# l297.net
KiCad netlist of a schematic drawn in EAGLE
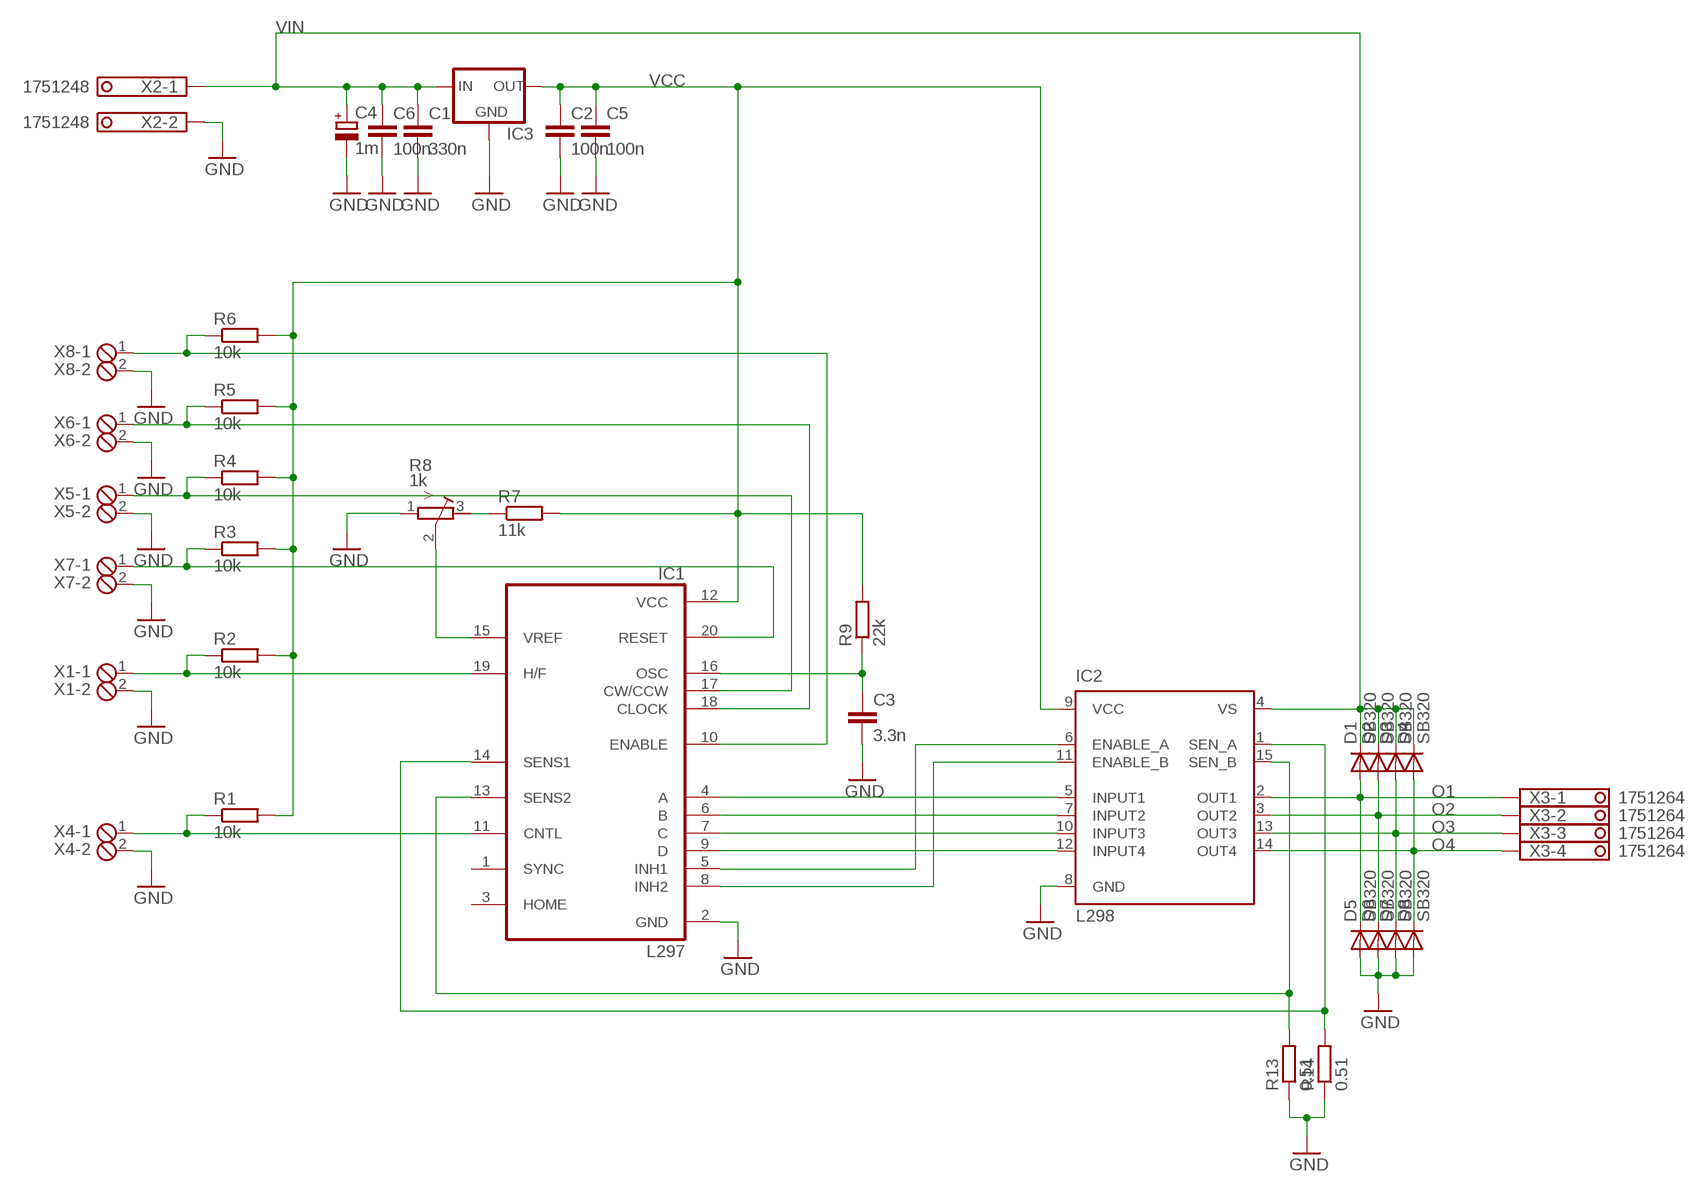
[diagram p0: schematic, sheet 1]

(export (version "E")
  (design (tool "Eeschema 10.0.6"))
  (components
    (comp (ref "C1")
      (value "330n")
      (footprint "eagle-import:C050-035X075")
      (libsource (lib "eagle-import") (part "C-EU050-035X075"))
    )
    (comp (ref "C2")
      (value "100n")
      (footprint "eagle-import:C050-035X075")
      (libsource (lib "eagle-import") (part "C-EU050-035X075"))
    )
    (comp (ref "C3")
      (value "3.3n")
      (footprint "eagle-import:C050-035X075")
      (libsource (lib "eagle-import") (part "C-EU050-035X075"))
    )
    (comp (ref "C4")
      (value "1m")
      (footprint "eagle-import:E5-13")
      (libsource (lib "eagle-import") (part "CPOL-EUE5-13"))
    )
    (comp (ref "C5")
      (value "100n")
      (footprint "eagle-import:C050-035X075")
      (libsource (lib "eagle-import") (part "C-EU050-035X075"))
    )
    (comp (ref "C6")
      (value "100n")
      (footprint "eagle-import:C050-035X075")
      (libsource (lib "eagle-import") (part "C-EU050-035X075"))
    )
    (comp (ref "D1")
      (value "SB320")
      (footprint "eagle-import:DO201-15")
      (libsource (lib "eagle-import") (part "SB320"))
    )
    (comp (ref "D2")
      (value "SB320")
      (footprint "eagle-import:DO201-15")
      (libsource (lib "eagle-import") (part "SB320"))
    )
    (comp (ref "D3")
      (value "SB320")
      (footprint "eagle-import:DO201-15")
      (libsource (lib "eagle-import") (part "SB320"))
    )
    (comp (ref "D4")
      (value "SB320")
      (footprint "eagle-import:DO201-15")
      (libsource (lib "eagle-import") (part "SB320"))
    )
    (comp (ref "D5")
      (value "SB320")
      (footprint "eagle-import:DO201-15")
      (libsource (lib "eagle-import") (part "SB320"))
    )
    (comp (ref "D6")
      (value "SB320")
      (footprint "eagle-import:DO201-15")
      (libsource (lib "eagle-import") (part "SB320"))
    )
    (comp (ref "D7")
      (value "SB320")
      (footprint "eagle-import:DO201-15")
      (libsource (lib "eagle-import") (part "SB320"))
    )
    (comp (ref "D8")
      (value "SB320")
      (footprint "eagle-import:DO201-15")
      (libsource (lib "eagle-import") (part "SB320"))
    )
    (comp (ref "IC1")
      (value "L297")
      (footprint "eagle-import:DIL20")
      (fields (field (name "MPN") "L297/1"))
      (libsource (lib "eagle-import") (part "L297"))
    )
    (comp (ref "IC2")
      (value "L298")
      (footprint "eagle-import:MULTIWATT-15")
      (fields (field (name "MPN") "L298N"))
      (libsource (lib "eagle-import") (part "L298"))
    )
    (comp (ref "IC3")
      (value "78XXS")
      (footprint "eagle-import:78XXS")
      (libsource (lib "eagle-import") (part "78XXS"))
    )
    (comp (ref "R1")
      (value "10k")
      (footprint "eagle-import:0207_10")
      (libsource (lib "eagle-import") (part "R-EU_0207/10"))
    )
    (comp (ref "R2")
      (value "10k")
      (footprint "eagle-import:0207_10")
      (libsource (lib "eagle-import") (part "R-EU_0207/10"))
    )
    (comp (ref "R3")
      (value "10k")
      (footprint "eagle-import:0207_10")
      (libsource (lib "eagle-import") (part "R-EU_0207/10"))
    )
    (comp (ref "R4")
      (value "10k")
      (footprint "eagle-import:0207_10")
      (libsource (lib "eagle-import") (part "R-EU_0207/10"))
    )
    (comp (ref "R5")
      (value "10k")
      (footprint "eagle-import:0207_10")
      (libsource (lib "eagle-import") (part "R-EU_0207/10"))
    )
    (comp (ref "R6")
      (value "10k")
      (footprint "eagle-import:0207_10")
      (libsource (lib "eagle-import") (part "R-EU_0207/10"))
    )
    (comp (ref "R7")
      (value "11k")
      (footprint "eagle-import:0207_10")
      (libsource (lib "eagle-import") (part "R-EU_0207/10"))
    )
    (comp (ref "R8")
      (value "1k")
      (footprint "eagle-import:RTRIM64W")
      (libsource (lib "eagle-import") (part "R-TRIMM64W"))
    )
    (comp (ref "R9")
      (value "22k")
      (footprint "eagle-import:0207_10")
      (libsource (lib "eagle-import") (part "R-EU_0207/10"))
    )
    (comp (ref "R13")
      (value "0.51")
      (footprint "eagle-import:0411_15")
      (libsource (lib "eagle-import") (part "R-EU_0411/15"))
    )
    (comp (ref "R14")
      (value "0.51")
      (footprint "eagle-import:0411_15")
      (libsource (lib "eagle-import") (part "R-EU_0411/15"))
    )
    (comp (ref "X1")
      (value "MPT2")
      (footprint "eagle-import:2POL254")
      (libsource (lib "eagle-import") (part "MPT2"))
    )
    (comp (ref "X2")
      (value "1751248")
      (footprint "eagle-import:1751248")
      (libsource (lib "eagle-import") (part "1751248"))
    )
    (comp (ref "X3")
      (value "1751264")
      (footprint "eagle-import:1751264")
      (libsource (lib "eagle-import") (part "1751264"))
    )
    (comp (ref "X4")
      (value "MPT2")
      (footprint "eagle-import:2POL254")
      (libsource (lib "eagle-import") (part "MPT2"))
    )
    (comp (ref "X5")
      (value "MPT2")
      (footprint "eagle-import:2POL254")
      (libsource (lib "eagle-import") (part "MPT2"))
    )
    (comp (ref "X6")
      (value "MPT2")
      (footprint "eagle-import:2POL254")
      (libsource (lib "eagle-import") (part "MPT2"))
    )
    (comp (ref "X7")
      (value "MPT2")
      (footprint "eagle-import:2POL254")
      (libsource (lib "eagle-import") (part "MPT2"))
    )
    (comp (ref "X8")
      (value "MPT2")
      (footprint "eagle-import:2POL254")
      (libsource (lib "eagle-import") (part "MPT2"))
    )
  )
  (nets
    (net (code "1") (name "/O1") (class "Default")
      (node (ref "D1") (pin "A") (pinfunction "A_A") (pintype "passive"))
      (node (ref "D5") (pin "C") (pinfunction "C_C") (pintype "passive"))
      (node (ref "IC2") (pin "2") (pinfunction "OUT1_2") (pintype "output"))
      (node (ref "X3") (pin "1") (pinfunction "K_1") (pintype "passive"))
    )
    (net (code "2") (name "/O2") (class "Default")
      (node (ref "D2") (pin "A") (pinfunction "A_A") (pintype "passive"))
      (node (ref "D6") (pin "C") (pinfunction "C_C") (pintype "passive"))
      (node (ref "IC2") (pin "3") (pinfunction "OUT2_3") (pintype "output"))
      (node (ref "X3") (pin "2") (pinfunction "K_2") (pintype "passive"))
    )
    (net (code "3") (name "/O3") (class "Default")
      (node (ref "D3") (pin "A") (pinfunction "A_A") (pintype "passive"))
      (node (ref "D7") (pin "C") (pinfunction "C_C") (pintype "passive"))
      (node (ref "IC2") (pin "13") (pinfunction "OUT3_13") (pintype "output"))
      (node (ref "X3") (pin "3") (pinfunction "K_3") (pintype "passive"))
    )
    (net (code "4") (name "/O4") (class "Default")
      (node (ref "D4") (pin "A") (pinfunction "A_A") (pintype "passive"))
      (node (ref "D8") (pin "C") (pinfunction "C_C") (pintype "passive"))
      (node (ref "IC2") (pin "14") (pinfunction "OUT4_14") (pintype "output"))
      (node (ref "X3") (pin "4") (pinfunction "K_4") (pintype "passive"))
    )
    (net (code "5") (name "/VCC") (class "Default")
      (node (ref "C2") (pin "1") (pinfunction "1_1") (pintype "passive"))
      (node (ref "C5") (pin "1") (pinfunction "1_1") (pintype "passive"))
      (node (ref "IC1") (pin "12") (pinfunction "VCC_12") (pintype "power_in"))
      (node (ref "IC2") (pin "9") (pinfunction "VCC_9") (pintype "power_in"))
      (node (ref "IC3") (pin "OUT") (pinfunction "OUT_OUT") (pintype "passive"))
      (node (ref "R1") (pin "2") (pinfunction "2_2") (pintype "passive"))
      (node (ref "R2") (pin "2") (pinfunction "2_2") (pintype "passive"))
      (node (ref "R3") (pin "2") (pinfunction "2_2") (pintype "passive"))
      (node (ref "R4") (pin "2") (pinfunction "2_2") (pintype "passive"))
      (node (ref "R5") (pin "2") (pinfunction "2_2") (pintype "passive"))
      (node (ref "R6") (pin "2") (pinfunction "2_2") (pintype "passive"))
      (node (ref "R7") (pin "2") (pinfunction "2_2") (pintype "passive"))
      (node (ref "R9") (pin "2") (pinfunction "2_2") (pintype "passive"))
    )
    (net (code "6") (name "/VIN") (class "Default")
      (node (ref "C1") (pin "1") (pinfunction "1_1") (pintype "passive"))
      (node (ref "C4") (pin "+") (pinfunction "+_+") (pintype "passive"))
      (node (ref "C6") (pin "1") (pinfunction "1_1") (pintype "passive"))
      (node (ref "D1") (pin "C") (pinfunction "C_C") (pintype "passive"))
      (node (ref "D2") (pin "C") (pinfunction "C_C") (pintype "passive"))
      (node (ref "D3") (pin "C") (pinfunction "C_C") (pintype "passive"))
      (node (ref "D4") (pin "C") (pinfunction "C_C") (pintype "passive"))
      (node (ref "IC2") (pin "4") (pinfunction "VS_4") (pintype "power_in"))
      (node (ref "IC3") (pin "IN") (pinfunction "IN_IN") (pintype "input"))
      (node (ref "X2") (pin "1") (pinfunction "K_1") (pintype "passive"))
    )
    (net (code "7") (name "GND") (class "Default")
      (node (ref "C1") (pin "2") (pinfunction "2_2") (pintype "passive"))
      (node (ref "C2") (pin "2") (pinfunction "2_2") (pintype "passive"))
      (node (ref "C3") (pin "2") (pinfunction "2_2") (pintype "passive"))
      (node (ref "C4") (pin "-") (pinfunction "-_-") (pintype "passive"))
      (node (ref "C5") (pin "2") (pinfunction "2_2") (pintype "passive"))
      (node (ref "C6") (pin "2") (pinfunction "2_2") (pintype "passive"))
      (node (ref "D5") (pin "A") (pinfunction "A_A") (pintype "passive"))
      (node (ref "D6") (pin "A") (pinfunction "A_A") (pintype "passive"))
      (node (ref "D7") (pin "A") (pinfunction "A_A") (pintype "passive"))
      (node (ref "D8") (pin "A") (pinfunction "A_A") (pintype "passive"))
      (node (ref "IC1") (pin "2") (pinfunction "GND_2") (pintype "power_in"))
      (node (ref "IC2") (pin "8") (pinfunction "GND_8") (pintype "power_in"))
      (node (ref "IC3") (pin "GND") (pinfunction "GND_GND") (pintype "input"))
      (node (ref "R13") (pin "1") (pinfunction "1_1") (pintype "passive"))
      (node (ref "R14") (pin "1") (pinfunction "1_1") (pintype "passive"))
      (node (ref "R8") (pin "1") (pinfunction "E_1") (pintype "passive"))
      (node (ref "X1") (pin "2") (pinfunction "1_2") (pintype "passive"))
      (node (ref "X2") (pin "2") (pinfunction "K_2") (pintype "passive"))
      (node (ref "X4") (pin "2") (pinfunction "1_2") (pintype "passive"))
      (node (ref "X5") (pin "2") (pinfunction "1_2") (pintype "passive"))
      (node (ref "X6") (pin "2") (pinfunction "1_2") (pintype "passive"))
      (node (ref "X7") (pin "2") (pinfunction "1_2") (pintype "passive"))
      (node (ref "X8") (pin "2") (pinfunction "1_2") (pintype "passive"))
    )
    (net (code "8") (name "Net-(IC1-A)") (class "Default")
      (node (ref "IC1") (pin "4") (pinfunction "A_4") (pintype "output"))
      (node (ref "IC2") (pin "5") (pinfunction "INPUT1_5") (pintype "input"))
    )
    (net (code "9") (name "Net-(IC1-B)") (class "Default")
      (node (ref "IC1") (pin "6") (pinfunction "B_6") (pintype "output"))
      (node (ref "IC2") (pin "7") (pinfunction "INPUT2_7") (pintype "input"))
    )
    (net (code "10") (name "Net-(IC1-C)") (class "Default")
      (node (ref "IC1") (pin "7") (pinfunction "C_7") (pintype "output"))
      (node (ref "IC2") (pin "10") (pinfunction "INPUT3_10") (pintype "input"))
    )
    (net (code "11") (name "Net-(IC1-CLOCK)") (class "Default")
      (node (ref "IC1") (pin "18") (pinfunction "CLOCK_18") (pintype "input"))
      (node (ref "R5") (pin "1") (pinfunction "1_1") (pintype "passive"))
      (node (ref "X6") (pin "1") (pinfunction "1_1") (pintype "passive"))
    )
    (net (code "12") (name "Net-(IC1-CNTL)") (class "Default")
      (node (ref "IC1") (pin "11") (pinfunction "CNTL_11") (pintype "input"))
      (node (ref "R1") (pin "1") (pinfunction "1_1") (pintype "passive"))
      (node (ref "X4") (pin "1") (pinfunction "1_1") (pintype "passive"))
    )
    (net (code "13") (name "Net-(IC1-CW{slash}CCW)") (class "Default")
      (node (ref "IC1") (pin "17") (pinfunction "CW/CCW_17") (pintype "input"))
      (node (ref "R4") (pin "1") (pinfunction "1_1") (pintype "passive"))
      (node (ref "X5") (pin "1") (pinfunction "1_1") (pintype "passive"))
    )
    (net (code "14") (name "Net-(IC1-D)") (class "Default")
      (node (ref "IC1") (pin "9") (pinfunction "D_9") (pintype "output"))
      (node (ref "IC2") (pin "12") (pinfunction "INPUT4_12") (pintype "input"))
    )
    (net (code "15") (name "Net-(IC1-ENABLE)") (class "Default")
      (node (ref "IC1") (pin "10") (pinfunction "ENABLE_10") (pintype "input"))
      (node (ref "R6") (pin "1") (pinfunction "1_1") (pintype "passive"))
      (node (ref "X8") (pin "1") (pinfunction "1_1") (pintype "passive"))
    )
    (net (code "16") (name "Net-(IC1-H{slash}F)") (class "Default")
      (node (ref "IC1") (pin "19") (pinfunction "H/F_19") (pintype "input"))
      (node (ref "R2") (pin "1") (pinfunction "1_1") (pintype "passive"))
      (node (ref "X1") (pin "1") (pinfunction "1_1") (pintype "passive"))
    )
    (net (code "17") (name "Net-(IC1-INH1)") (class "Default")
      (node (ref "IC1") (pin "5") (pinfunction "INH1_5") (pintype "output"))
      (node (ref "IC2") (pin "6") (pinfunction "ENABLE_A_6") (pintype "input"))
    )
    (net (code "18") (name "Net-(IC1-INH2)") (class "Default")
      (node (ref "IC1") (pin "8") (pinfunction "INH2_8") (pintype "output"))
      (node (ref "IC2") (pin "11") (pinfunction "ENABLE_B_11") (pintype "input"))
    )
    (net (code "19") (name "Net-(IC1-OSC)") (class "Default")
      (node (ref "C3") (pin "1") (pinfunction "1_1") (pintype "passive"))
      (node (ref "IC1") (pin "16") (pinfunction "OSC_16") (pintype "bidirectional"))
      (node (ref "R9") (pin "1") (pinfunction "1_1") (pintype "passive"))
    )
    (net (code "20") (name "Net-(IC1-RESET)") (class "Default")
      (node (ref "IC1") (pin "20") (pinfunction "RESET_20") (pintype "input"))
      (node (ref "R3") (pin "1") (pinfunction "1_1") (pintype "passive"))
      (node (ref "X7") (pin "1") (pinfunction "1_1") (pintype "passive"))
    )
    (net (code "21") (name "Net-(IC1-SENS1)") (class "Default")
      (node (ref "IC1") (pin "14") (pinfunction "SENS1_14") (pintype "output"))
      (node (ref "IC2") (pin "1") (pinfunction "SEN_A_1") (pintype "input"))
      (node (ref "R14") (pin "2") (pinfunction "2_2") (pintype "passive"))
    )
    (net (code "22") (name "Net-(IC1-SENS2)") (class "Default")
      (node (ref "IC1") (pin "13") (pinfunction "SENS2_13") (pintype "output"))
      (node (ref "IC2") (pin "15") (pinfunction "SEN_B_15") (pintype "input"))
      (node (ref "R13") (pin "2") (pinfunction "2_2") (pintype "passive"))
    )
    (net (code "23") (name "Net-(IC1-VREF)") (class "Default")
      (node (ref "IC1") (pin "15") (pinfunction "VREF_15") (pintype "input"))
      (node (ref "R8") (pin "2") (pinfunction "S_2") (pintype "passive"))
    )
    (net (code "24") (name "Net-(R8-A)") (class "Default")
      (node (ref "R7") (pin "1") (pinfunction "1_1") (pintype "passive"))
      (node (ref "R8") (pin "3") (pinfunction "A_3") (pintype "passive"))
    )
    (net (code "25") (name "unconnected-(IC1-HOME-Pad3)") (class "Default")
      (node (ref "IC1") (pin "3") (pinfunction "HOME_3") (pintype "output"))
    )
    (net (code "26") (name "unconnected-(IC1-SYNC-Pad1)") (class "Default")
      (node (ref "IC1") (pin "1") (pinfunction "SYNC_1") (pintype "output"))
    )
  )
)
